# tinyha_power.net
KiCad netlist of a schematic drawn in EAGLE
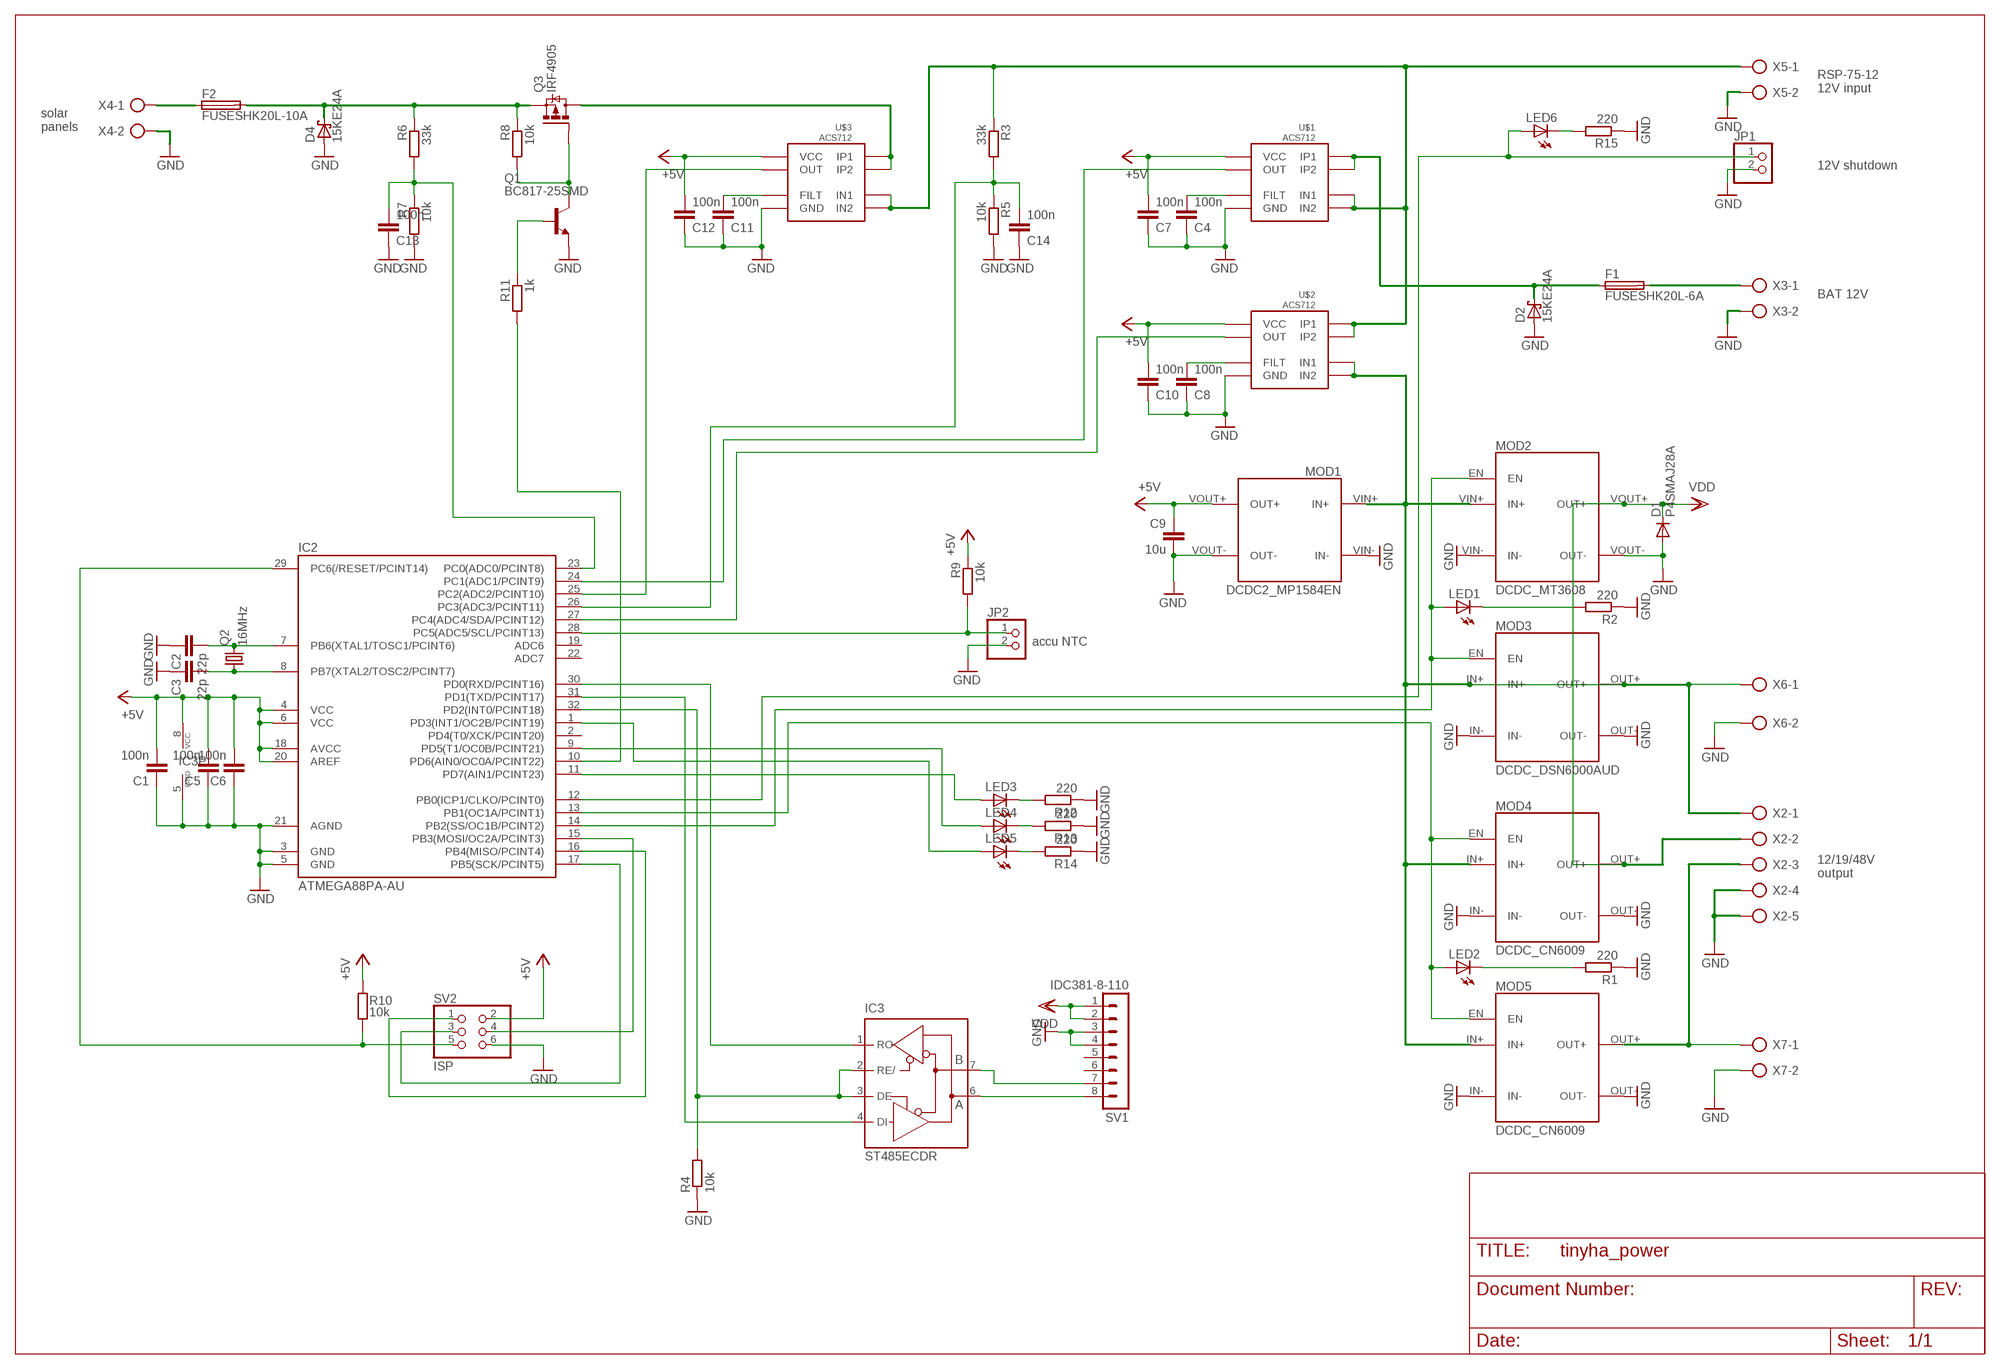
[diagram p0: schematic, sheet 1]

(export (version "E")
  (design (tool "Eeschema 10.0.6"))
  (components
    (comp (ref "C1")
      (value "100n")
      (footprint "eagle-import:C0805K")
      (libsource (lib "eagle-import") (part "C-EUC0805K"))
    )
    (comp (ref "C2")
      (value "22p")
      (footprint "eagle-import:C0805K")
      (libsource (lib "eagle-import") (part "C-EUC0805K"))
    )
    (comp (ref "C3")
      (value "22p")
      (footprint "eagle-import:C0805K")
      (libsource (lib "eagle-import") (part "C-EUC0805K"))
    )
    (comp (ref "C4")
      (value "100n")
      (footprint "eagle-import:C0805")
      (libsource (lib "eagle-import") (part "C-EUC0805"))
    )
    (comp (ref "C5")
      (value "100n")
      (footprint "eagle-import:C0805K")
      (libsource (lib "eagle-import") (part "C-EUC0805K"))
    )
    (comp (ref "C6")
      (value "100n")
      (footprint "eagle-import:C0805K")
      (libsource (lib "eagle-import") (part "C-EUC0805K"))
    )
    (comp (ref "C7")
      (value "100n")
      (footprint "eagle-import:C0805")
      (libsource (lib "eagle-import") (part "C-EUC0805"))
    )
    (comp (ref "C8")
      (value "100n")
      (footprint "eagle-import:C0805")
      (libsource (lib "eagle-import") (part "C-EUC0805"))
    )
    (comp (ref "C9")
      (value "10u")
      (footprint "eagle-import:C0805K")
      (libsource (lib "eagle-import") (part "C-EUC0805K"))
    )
    (comp (ref "C10")
      (value "100n")
      (footprint "eagle-import:C0805")
      (libsource (lib "eagle-import") (part "C-EUC0805"))
    )
    (comp (ref "C11")
      (value "100n")
      (footprint "eagle-import:C0805")
      (libsource (lib "eagle-import") (part "C-EUC0805"))
    )
    (comp (ref "C12")
      (value "100n")
      (footprint "eagle-import:C0805")
      (libsource (lib "eagle-import") (part "C-EUC0805"))
    )
    (comp (ref "C13")
      (value "100n")
      (footprint "eagle-import:C0805")
      (libsource (lib "eagle-import") (part "C-EUC0805"))
    )
    (comp (ref "C14")
      (value "100n")
      (footprint "eagle-import:C0805")
      (libsource (lib "eagle-import") (part "C-EUC0805"))
    )
    (comp (ref "D1")
      (value "P4SMAJ28A")
      (footprint "eagle-import:DO214AC")
      (libsource (lib "eagle-import") (part "DIODE-DO214AC"))
    )
    (comp (ref "D2")
      (value "15KE24A")
      (footprint "eagle-import:CB429-17")
      (libsource (lib "eagle-import") (part "15KEXX"))
    )
    (comp (ref "D4")
      (value "15KE24A")
      (footprint "eagle-import:CB429-17")
      (libsource (lib "eagle-import") (part "15KEXX"))
    )
    (comp (ref "F1")
      (value "FUSESHK20L-6A")
      (footprint "eagle-import:SHK20L")
      (libsource (lib "eagle-import") (part "FUSESHK20L"))
    )
    (comp (ref "F2")
      (value "FUSESHK20L-10A")
      (footprint "eagle-import:SHK20L")
      (libsource (lib "eagle-import") (part "FUSESHK20L"))
    )
    (comp (ref "IC2")
      (value "ATMEGA88PA-AU")
      (footprint "eagle-import:TQFP32-08")
      (libsource (lib "eagle-import") (part "ATMEGA48/88/168-AU"))
    )
    (comp (ref "IC3")
      (value "ST485ECDR")
      (footprint "eagle-import:SO08")
      (fields (field (name "MF") "MAXIM") (field (name "MPN") "MAX481CSA"))
      (libsource (lib "eagle-import") (part "MAX481CSA"))
    )
    (comp (ref "JP1")
      (value "PINHD-1X2")
      (footprint "eagle-import:1X02")
      (libsource (lib "eagle-import") (part "PINHD-1X2"))
    )
    (comp (ref "JP2")
      (value "PINHD-1X2")
      (footprint "eagle-import:1X02")
      (libsource (lib "eagle-import") (part "PINHD-1X2"))
    )
    (comp (ref "LED1")
      (value "LED3MM")
      (footprint "eagle-import:LED3MM")
      (libsource (lib "eagle-import") (part "LED3MM"))
    )
    (comp (ref "LED2")
      (value "LED3MM")
      (footprint "eagle-import:LED3MM")
      (libsource (lib "eagle-import") (part "LED3MM"))
    )
    (comp (ref "LED3")
      (value "LED3MM")
      (footprint "eagle-import:LED3MM")
      (libsource (lib "eagle-import") (part "LED3MM"))
    )
    (comp (ref "LED4")
      (value "LED3MM")
      (footprint "eagle-import:LED3MM")
      (libsource (lib "eagle-import") (part "LED3MM"))
    )
    (comp (ref "LED5")
      (value "LED3MM")
      (footprint "eagle-import:LED3MM")
      (libsource (lib "eagle-import") (part "LED3MM"))
    )
    (comp (ref "LED6")
      (value "LED3MM")
      (footprint "eagle-import:LED3MM")
      (libsource (lib "eagle-import") (part "LED3MM"))
    )
    (comp (ref "MOD1")
      (value "DCDC2_MP1584EN")
      (footprint "eagle-import:DCDC_MP1584EN")
      (libsource (lib "eagle-import") (part "DCDC2_MP1584EN"))
    )
    (comp (ref "MOD2")
      (value "DCDC_MT3608")
      (footprint "eagle-import:DCDC_MT3608")
      (libsource (lib "eagle-import") (part "DCDC_MT3608"))
    )
    (comp (ref "MOD3")
      (value "DCDC_DSN6000AUD")
      (footprint "eagle-import:DCDC_DSN6000AUD")
      (libsource (lib "eagle-import") (part "DCDC_DSN6000AUD"))
    )
    (comp (ref "MOD4")
      (value "DCDC_CN6009")
      (footprint "eagle-import:DCDC_CN6009")
      (libsource (lib "eagle-import") (part "DCDC_CN6009"))
    )
    (comp (ref "MOD5")
      (value "DCDC_CN6009")
      (footprint "eagle-import:DCDC_CN6009")
      (libsource (lib "eagle-import") (part "DCDC_CN6009"))
    )
    (comp (ref "Q1")
      (value "BC817-25SMD")
      (footprint "eagle-import:SOT23-BEC")
      (libsource (lib "eagle-import") (part "BC817SMD-25"))
    )
    (comp (ref "Q2")
      (value "16MHz")
      (footprint "eagle-import:HC49_S")
      (libsource (lib "eagle-import") (part "CRYSTALHC49S"))
    )
    (comp (ref "Q3")
      (value "IRF4905")
      (footprint "eagle-import:TO220BH")
      (libsource (lib "eagle-import") (part "IRF4905"))
    )
    (comp (ref "R1")
      (value "220")
      (footprint "eagle-import:R0805")
      (libsource (lib "eagle-import") (part "R-EU_R0805"))
    )
    (comp (ref "R2")
      (value "220")
      (footprint "eagle-import:R0805")
      (libsource (lib "eagle-import") (part "R-EU_R0805"))
    )
    (comp (ref "R3")
      (value "33k")
      (footprint "eagle-import:R0805")
      (libsource (lib "eagle-import") (part "R-EU_R0805"))
    )
    (comp (ref "R4")
      (value "10k")
      (footprint "eagle-import:R0805")
      (libsource (lib "eagle-import") (part "R-EU_R0805"))
    )
    (comp (ref "R5")
      (value "10k")
      (footprint "eagle-import:R0805")
      (libsource (lib "eagle-import") (part "R-EU_R0805"))
    )
    (comp (ref "R6")
      (value "33k")
      (footprint "eagle-import:R0805")
      (libsource (lib "eagle-import") (part "R-EU_R0805"))
    )
    (comp (ref "R7")
      (value "10k")
      (footprint "eagle-import:R0805")
      (libsource (lib "eagle-import") (part "R-EU_R0805"))
    )
    (comp (ref "R8")
      (value "10k")
      (footprint "eagle-import:R0805")
      (libsource (lib "eagle-import") (part "R-EU_R0805"))
    )
    (comp (ref "R9")
      (value "10k")
      (footprint "eagle-import:R0805")
      (libsource (lib "eagle-import") (part "R-EU_R0805"))
    )
    (comp (ref "R10")
      (value "10k")
      (footprint "eagle-import:R0805")
      (libsource (lib "eagle-import") (part "R-EU_R0805"))
    )
    (comp (ref "R11")
      (value "1k")
      (footprint "eagle-import:R0805")
      (libsource (lib "eagle-import") (part "R-EU_R0805"))
    )
    (comp (ref "R12")
      (value "220")
      (footprint "eagle-import:R0805")
      (libsource (lib "eagle-import") (part "R-EU_R0805"))
    )
    (comp (ref "R13")
      (value "220")
      (footprint "eagle-import:R0805")
      (libsource (lib "eagle-import") (part "R-EU_R0805"))
    )
    (comp (ref "R14")
      (value "220")
      (footprint "eagle-import:R0805")
      (libsource (lib "eagle-import") (part "R-EU_R0805"))
    )
    (comp (ref "R15")
      (value "220")
      (footprint "eagle-import:R0805")
      (libsource (lib "eagle-import") (part "R-EU_R0805"))
    )
    (comp (ref "SV1")
      (value "IDC381-8-110")
      (footprint "eagle-import:IDC381-8")
      (libsource (lib "eagle-import") (part "MA08-1-IDC"))
    )
    (comp (ref "SV2")
      (value "ISP")
      (footprint "eagle-import:2X03_H")
      (libsource (lib "eagle-import") (part "PINHD-2X3/H"))
    )
    (comp (ref "U$1")
      (value "ACS712")
      (footprint "eagle-import:SO8")
      (libsource (lib "eagle-import") (part "ACS712"))
    )
    (comp (ref "U$2")
      (value "ACS712")
      (footprint "eagle-import:SO8")
      (libsource (lib "eagle-import") (part "ACS712"))
    )
    (comp (ref "U$3")
      (value "ACS712")
      (footprint "eagle-import:SO8")
      (libsource (lib "eagle-import") (part "ACS712"))
    )
    (comp (ref "X2")
      (value "AK500/5")
      (footprint "eagle-import:AK500_5")
      (libsource (lib "eagle-import") (part "AK500/5"))
    )
    (comp (ref "X3")
      (value "AK500/2")
      (footprint "eagle-import:AK500_2")
      (libsource (lib "eagle-import") (part "AK500/2"))
    )
    (comp (ref "X4")
      (value "AK500/2")
      (footprint "eagle-import:AK500_2")
      (libsource (lib "eagle-import") (part "AK500/2"))
    )
    (comp (ref "X5")
      (value "AK500/2")
      (footprint "eagle-import:AK500_2")
      (libsource (lib "eagle-import") (part "AK500/2"))
    )
    (comp (ref "X6")
      (value "AK500/2")
      (footprint "eagle-import:AK500_2")
      (libsource (lib "eagle-import") (part "AK500/2"))
    )
    (comp (ref "X7")
      (value "AK500/2")
      (footprint "eagle-import:AK500_2")
      (libsource (lib "eagle-import") (part "AK500/2"))
    )
  )
  (nets
    (net (code "1") (name "+5V") (class "Default")
      (node (ref "C1") (pin "2") (pinfunction "2_2") (pintype "passive"))
      (node (ref "C10") (pin "2") (pinfunction "2_2") (pintype "passive"))
      (node (ref "C12") (pin "2") (pinfunction "2_2") (pintype "passive"))
      (node (ref "C5") (pin "2") (pinfunction "2_2") (pintype "passive"))
      (node (ref "C6") (pin "2") (pinfunction "2_2") (pintype "passive"))
      (node (ref "C7") (pin "2") (pinfunction "2_2") (pintype "passive"))
      (node (ref "C9") (pin "1") (pinfunction "1_1") (pintype "passive"))
      (node (ref "IC2") (pin "18") (pinfunction "AVCC_18") (pintype "passive"))
      (node (ref "IC2") (pin "20") (pinfunction "AREF_20") (pintype "passive"))
      (node (ref "IC2") (pin "4") (pinfunction "VCC_4") (pintype "power_in"))
      (node (ref "IC2") (pin "6") (pinfunction "VCC_6") (pintype "power_in"))
      (node (ref "IC3") (pin "8") (pinfunction "VCC_8") (pintype "power_in"))
      (node (ref "MOD1") (pin "VOUT+") (pinfunction "OUT+_VOUT+") (pintype "passive"))
      (node (ref "R10") (pin "1") (pinfunction "1_1") (pintype "passive"))
      (node (ref "R9") (pin "1") (pinfunction "1_1") (pintype "passive"))
      (node (ref "SV2") (pin "2") (pinfunction "2_2") (pintype "passive"))
      (node (ref "U$1") (pin "8") (pinfunction "VCC_8") (pintype "bidirectional"))
      (node (ref "U$2") (pin "8") (pinfunction "VCC_8") (pintype "bidirectional"))
      (node (ref "U$3") (pin "8") (pinfunction "VCC_8") (pintype "bidirectional"))
    )
    (net (code "2") (name "GND") (class "Default")
      (node (ref "C1") (pin "1") (pinfunction "1_1") (pintype "passive"))
      (node (ref "C10") (pin "1") (pinfunction "1_1") (pintype "passive"))
      (node (ref "C11") (pin "1") (pinfunction "1_1") (pintype "passive"))
      (node (ref "C12") (pin "1") (pinfunction "1_1") (pintype "passive"))
      (node (ref "C13") (pin "1") (pinfunction "1_1") (pintype "passive"))
      (node (ref "C14") (pin "1") (pinfunction "1_1") (pintype "passive"))
      (node (ref "C2") (pin "1") (pinfunction "1_1") (pintype "passive"))
      (node (ref "C3") (pin "1") (pinfunction "1_1") (pintype "passive"))
      (node (ref "C4") (pin "1") (pinfunction "1_1") (pintype "passive"))
      (node (ref "C5") (pin "1") (pinfunction "1_1") (pintype "passive"))
      (node (ref "C6") (pin "1") (pinfunction "1_1") (pintype "passive"))
      (node (ref "C7") (pin "1") (pinfunction "1_1") (pintype "passive"))
      (node (ref "C8") (pin "1") (pinfunction "1_1") (pintype "passive"))
      (node (ref "C9") (pin "2") (pinfunction "2_2") (pintype "passive"))
      (node (ref "D1") (pin "A") (pinfunction "A_A") (pintype "passive"))
      (node (ref "D2") (pin "A") (pinfunction "A_A") (pintype "passive"))
      (node (ref "D4") (pin "A") (pinfunction "A_A") (pintype "passive"))
      (node (ref "IC2") (pin "21") (pinfunction "AGND_21") (pintype "power_in"))
      (node (ref "IC2") (pin "3") (pinfunction "GND_3") (pintype "power_in"))
      (node (ref "IC2") (pin "5") (pinfunction "GND_5") (pintype "power_in"))
      (node (ref "IC3") (pin "5") (pinfunction "GND_5") (pintype "power_in"))
      (node (ref "JP1") (pin "2") (pinfunction "2_2") (pintype "passive"))
      (node (ref "JP2") (pin "2") (pinfunction "2_2") (pintype "passive"))
      (node (ref "MOD1") (pin "VIN-") (pinfunction "IN-_VIN-") (pintype "passive"))
      (node (ref "MOD1") (pin "VOUT-") (pinfunction "OUT-_VOUT-") (pintype "passive"))
      (node (ref "MOD2") (pin "VIN-") (pinfunction "IN-_VIN-") (pintype "passive"))
      (node (ref "MOD2") (pin "VOUT-") (pinfunction "OUT-_VOUT-") (pintype "passive"))
      (node (ref "MOD3") (pin "IN-") (pinfunction "IN-_IN-") (pintype "passive"))
      (node (ref "MOD3") (pin "OUT-") (pinfunction "OUT-_OUT-") (pintype "passive"))
      (node (ref "MOD4") (pin "IN-") (pinfunction "IN-_IN-") (pintype "passive"))
      (node (ref "MOD4") (pin "OUT-") (pinfunction "OUT-_OUT-") (pintype "passive"))
      (node (ref "MOD5") (pin "IN-") (pinfunction "IN-_IN-") (pintype "passive"))
      (node (ref "MOD5") (pin "OUT-") (pinfunction "OUT-_OUT-") (pintype "passive"))
      (node (ref "Q1") (pin "E") (pinfunction "E_E") (pintype "passive"))
      (node (ref "R1") (pin "1") (pinfunction "1_1") (pintype "passive"))
      (node (ref "R12") (pin "1") (pinfunction "1_1") (pintype "passive"))
      (node (ref "R13") (pin "1") (pinfunction "1_1") (pintype "passive"))
      (node (ref "R14") (pin "1") (pinfunction "1_1") (pintype "passive"))
      (node (ref "R15") (pin "1") (pinfunction "1_1") (pintype "passive"))
      (node (ref "R2") (pin "1") (pinfunction "1_1") (pintype "passive"))
      (node (ref "R4") (pin "1") (pinfunction "1_1") (pintype "passive"))
      (node (ref "R5") (pin "2") (pinfunction "2_2") (pintype "passive"))
      (node (ref "R7") (pin "2") (pinfunction "2_2") (pintype "passive"))
      (node (ref "SV1") (pin "3") (pinfunction "3_3") (pintype "passive"))
      (node (ref "SV1") (pin "4") (pinfunction "4_4") (pintype "passive"))
      (node (ref "SV2") (pin "6") (pinfunction "6_6") (pintype "passive"))
      (node (ref "U$1") (pin "5") (pinfunction "GND_5") (pintype "bidirectional"))
      (node (ref "U$2") (pin "5") (pinfunction "GND_5") (pintype "bidirectional"))
      (node (ref "U$3") (pin "5") (pinfunction "GND_5") (pintype "bidirectional"))
      (node (ref "X2") (pin "4") (pinfunction "KL_4") (pintype "passive"))
      (node (ref "X2") (pin "5") (pinfunction "KL_5") (pintype "passive"))
      (node (ref "X3") (pin "2") (pinfunction "KL_2") (pintype "passive"))
      (node (ref "X4") (pin "2") (pinfunction "KL_2") (pintype "passive"))
      (node (ref "X5") (pin "2") (pinfunction "KL_2") (pintype "passive"))
      (node (ref "X6") (pin "2") (pinfunction "KL_2") (pintype "passive"))
      (node (ref "X7") (pin "2") (pinfunction "KL_2") (pintype "passive"))
    )
    (net (code "3") (name "Net-(F1-1)") (class "Default")
      (node (ref "D2") (pin "C") (pinfunction "C_C") (pintype "passive"))
      (node (ref "F1") (pin "1A") (pinfunction "1_1A") (pintype "passive"))
      (node (ref "U$1") (pin "1") (pinfunction "IP1_1") (pintype "bidirectional"))
      (node (ref "U$1") (pin "2") (pinfunction "IP2_2") (pintype "bidirectional"))
    )
    (net (code "4") (name "Net-(F1-2)") (class "Default")
      (node (ref "F1") (pin "2A") (pinfunction "2_2A") (pintype "passive"))
      (node (ref "X3") (pin "1") (pinfunction "KL_1") (pintype "passive"))
    )
    (net (code "5") (name "Net-(F2-1)") (class "Default")
      (node (ref "F2") (pin "1A") (pinfunction "1_1A") (pintype "passive"))
      (node (ref "X4") (pin "1") (pinfunction "KL_1") (pintype "passive"))
    )
    (net (code "6") (name "Net-(F2-2)") (class "Default")
      (node (ref "D4") (pin "C") (pinfunction "C_C") (pintype "passive"))
      (node (ref "F2") (pin "2A") (pinfunction "2_2A") (pintype "passive"))
      (node (ref "Q3") (pin "S") (pinfunction "S_S") (pintype "passive"))
      (node (ref "R6") (pin "1") (pinfunction "1_1") (pintype "passive"))
      (node (ref "R8") (pin "1") (pinfunction "1_1") (pintype "passive"))
    )
    (net (code "7") (name "Net-(IC2-PB0(ICP1{slash}CLKO{slash}PCINT0))") (class "Default")
      (node (ref "IC2") (pin "12") (pinfunction "PB0(ICP1/CLKO/PCINT0)_12") (pintype "bidirectional"))
      (node (ref "JP1") (pin "1") (pinfunction "1_1") (pintype "passive"))
      (node (ref "LED6") (pin "A") (pinfunction "A_A") (pintype "passive"))
    )
    (net (code "8") (name "Net-(IC2-PB1(OC1A{slash}PCINT1))") (class "Default")
      (node (ref "IC2") (pin "13") (pinfunction "PB1(OC1A/PCINT1)_13") (pintype "bidirectional"))
      (node (ref "LED2") (pin "A") (pinfunction "A_A") (pintype "passive"))
      (node (ref "MOD4") (pin "EN") (pinfunction "EN_EN") (pintype "input"))
      (node (ref "MOD5") (pin "EN") (pinfunction "EN_EN") (pintype "input"))
    )
    (net (code "9") (name "Net-(IC2-PB2(SS{slash}OC1B{slash}PCINT2))") (class "Default")
      (node (ref "IC2") (pin "14") (pinfunction "PB2(SS/OC1B/PCINT2)_14") (pintype "bidirectional"))
      (node (ref "LED1") (pin "A") (pinfunction "A_A") (pintype "passive"))
      (node (ref "MOD2") (pin "EN") (pinfunction "EN_EN") (pintype "input"))
      (node (ref "MOD3") (pin "EN") (pinfunction "EN_EN") (pintype "input"))
    )
    (net (code "10") (name "Net-(IC2-PB3(MOSI{slash}OC2A{slash}PCINT3))") (class "Default")
      (node (ref "IC2") (pin "15") (pinfunction "PB3(MOSI/OC2A/PCINT3)_15") (pintype "bidirectional"))
      (node (ref "SV2") (pin "4") (pinfunction "4_4") (pintype "passive"))
    )
    (net (code "11") (name "Net-(IC2-PB4(MISO{slash}PCINT4))") (class "Default")
      (node (ref "IC2") (pin "16") (pinfunction "PB4(MISO/PCINT4)_16") (pintype "bidirectional"))
      (node (ref "SV2") (pin "1") (pinfunction "1_1") (pintype "passive"))
    )
    (net (code "12") (name "Net-(IC2-PB5(SCK{slash}PCINT5))") (class "Default")
      (node (ref "IC2") (pin "17") (pinfunction "PB5(SCK/PCINT5)_17") (pintype "bidirectional"))
      (node (ref "SV2") (pin "3") (pinfunction "3_3") (pintype "passive"))
    )
    (net (code "13") (name "Net-(IC2-PB6(XTAL1{slash}TOSC1{slash}PCINT6))") (class "Default")
      (node (ref "C2") (pin "2") (pinfunction "2_2") (pintype "passive"))
      (node (ref "IC2") (pin "7") (pinfunction "PB6(XTAL1/TOSC1/PCINT6)_7") (pintype "bidirectional"))
      (node (ref "Q2") (pin "2") (pinfunction "2_2") (pintype "passive"))
    )
    (net (code "14") (name "Net-(IC2-PB7(XTAL2{slash}TOSC2{slash}PCINT7))") (class "Default")
      (node (ref "C3") (pin "2") (pinfunction "2_2") (pintype "passive"))
      (node (ref "IC2") (pin "8") (pinfunction "PB7(XTAL2/TOSC2/PCINT7)_8") (pintype "bidirectional"))
      (node (ref "Q2") (pin "1") (pinfunction "1_1") (pintype "passive"))
    )
    (net (code "15") (name "Net-(IC2-PC0(ADC0{slash}PCINT8))") (class "Default")
      (node (ref "C13") (pin "2") (pinfunction "2_2") (pintype "passive"))
      (node (ref "IC2") (pin "23") (pinfunction "PC0(ADC0/PCINT8)_23") (pintype "bidirectional"))
      (node (ref "R6") (pin "2") (pinfunction "2_2") (pintype "passive"))
      (node (ref "R7") (pin "1") (pinfunction "1_1") (pintype "passive"))
    )
    (net (code "16") (name "Net-(IC2-PC1(ADC1{slash}PCINT9))") (class "Default")
      (node (ref "IC2") (pin "24") (pinfunction "PC1(ADC1/PCINT9)_24") (pintype "bidirectional"))
      (node (ref "U$1") (pin "7") (pinfunction "OUT_7") (pintype "bidirectional"))
    )
    (net (code "17") (name "Net-(IC2-PC2(ADC2{slash}PCINT10))") (class "Default")
      (node (ref "IC2") (pin "25") (pinfunction "PC2(ADC2/PCINT10)_25") (pintype "bidirectional"))
      (node (ref "U$3") (pin "7") (pinfunction "OUT_7") (pintype "bidirectional"))
    )
    (net (code "18") (name "Net-(IC2-PC3(ADC3{slash}PCINT11))") (class "Default")
      (node (ref "C14") (pin "2") (pinfunction "2_2") (pintype "passive"))
      (node (ref "IC2") (pin "26") (pinfunction "PC3(ADC3/PCINT11)_26") (pintype "bidirectional"))
      (node (ref "R3") (pin "2") (pinfunction "2_2") (pintype "passive"))
      (node (ref "R5") (pin "1") (pinfunction "1_1") (pintype "passive"))
    )
    (net (code "19") (name "Net-(IC2-PC4(ADC4{slash}SDA{slash}PCINT12))") (class "Default")
      (node (ref "IC2") (pin "27") (pinfunction "PC4(ADC4/SDA/PCINT12)_27") (pintype "bidirectional"))
      (node (ref "U$2") (pin "7") (pinfunction "OUT_7") (pintype "bidirectional"))
    )
    (net (code "20") (name "Net-(IC2-PC5(ADC5{slash}SCL{slash}PCINT13))") (class "Default")
      (node (ref "IC2") (pin "28") (pinfunction "PC5(ADC5/SCL/PCINT13)_28") (pintype "bidirectional"))
      (node (ref "JP2") (pin "1") (pinfunction "1_1") (pintype "passive"))
      (node (ref "R9") (pin "2") (pinfunction "2_2") (pintype "passive"))
    )
    (net (code "21") (name "Net-(IC2-PC6({slash}RESET{slash}PCINT14))") (class "Default")
      (node (ref "IC2") (pin "29") (pinfunction "PC6(/RESET/PCINT14)_29") (pintype "bidirectional"))
      (node (ref "R10") (pin "2") (pinfunction "2_2") (pintype "passive"))
      (node (ref "SV2") (pin "5") (pinfunction "5_5") (pintype "passive"))
    )
    (net (code "22") (name "Net-(IC2-PD0(RXD{slash}PCINT16))") (class "Default")
      (node (ref "IC2") (pin "30") (pinfunction "PD0(RXD/PCINT16)_30") (pintype "bidirectional"))
      (node (ref "IC3") (pin "1") (pinfunction "RO_1") (pintype "output"))
    )
    (net (code "23") (name "Net-(IC2-PD1(TXD{slash}PCINT17))") (class "Default")
      (node (ref "IC2") (pin "31") (pinfunction "PD1(TXD/PCINT17)_31") (pintype "bidirectional"))
      (node (ref "IC3") (pin "4") (pinfunction "DI_4") (pintype "input"))
    )
    (net (code "24") (name "Net-(IC2-PD2(INT0{slash}PCINT18))") (class "Default")
      (node (ref "IC2") (pin "32") (pinfunction "PD2(INT0/PCINT18)_32") (pintype "bidirectional"))
      (node (ref "IC3") (pin "2") (pinfunction "RE/_2") (pintype "input"))
      (node (ref "IC3") (pin "3") (pinfunction "DE_3") (pintype "input"))
      (node (ref "R4") (pin "2") (pinfunction "2_2") (pintype "passive"))
    )
    (net (code "25") (name "Net-(IC2-PD3(INT1{slash}OC2B{slash}PCINT19))") (class "Default")
      (node (ref "IC2") (pin "1") (pinfunction "PD3(INT1/OC2B/PCINT19)_1") (pintype "bidirectional"))
      (node (ref "LED5") (pin "A") (pinfunction "A_A") (pintype "passive"))
    )
    (net (code "26") (name "Net-(IC2-PD5(T1{slash}OC0B{slash}PCINT21))") (class "Default")
      (node (ref "IC2") (pin "9") (pinfunction "PD5(T1/OC0B/PCINT21)_9") (pintype "bidirectional"))
      (node (ref "LED4") (pin "A") (pinfunction "A_A") (pintype "passive"))
    )
    (net (code "27") (name "Net-(IC2-PD6(AIN0{slash}OC0A{slash}PCINT22))") (class "Default")
      (node (ref "IC2") (pin "10") (pinfunction "PD6(AIN0/OC0A/PCINT22)_10") (pintype "bidirectional"))
      (node (ref "R11") (pin "2") (pinfunction "2_2") (pintype "passive"))
    )
    (net (code "28") (name "Net-(IC2-PD7(AIN1{slash}PCINT23))") (class "Default")
      (node (ref "IC2") (pin "11") (pinfunction "PD7(AIN1/PCINT23)_11") (pintype "bidirectional"))
      (node (ref "LED3") (pin "A") (pinfunction "A_A") (pintype "passive"))
    )
    (net (code "29") (name "Net-(IC3A-A)") (class "Default")
      (node (ref "IC3") (pin "6") (pinfunction "A_6") (pintype "passive"))
      (node (ref "SV1") (pin "8") (pinfunction "8_8") (pintype "passive"))
    )
    (net (code "30") (name "Net-(IC3A-B)") (class "Default")
      (node (ref "IC3") (pin "7") (pinfunction "B_7") (pintype "passive"))
      (node (ref "SV1") (pin "7") (pinfunction "7_7") (pintype "passive"))
    )
    (net (code "31") (name "Net-(LED1-C)") (class "Default")
      (node (ref "LED1") (pin "K") (pinfunction "C_K") (pintype "passive"))
      (node (ref "R2") (pin "2") (pinfunction "2_2") (pintype "passive"))
    )
    (net (code "32") (name "Net-(LED2-C)") (class "Default")
      (node (ref "LED2") (pin "K") (pinfunction "C_K") (pintype "passive"))
      (node (ref "R1") (pin "2") (pinfunction "2_2") (pintype "passive"))
    )
    (net (code "33") (name "Net-(LED3-C)") (class "Default")
      (node (ref "LED3") (pin "K") (pinfunction "C_K") (pintype "passive"))
      (node (ref "R12") (pin "2") (pinfunction "2_2") (pintype "passive"))
    )
    (net (code "34") (name "Net-(LED4-C)") (class "Default")
      (node (ref "LED4") (pin "K") (pinfunction "C_K") (pintype "passive"))
      (node (ref "R13") (pin "2") (pinfunction "2_2") (pintype "passive"))
    )
    (net (code "35") (name "Net-(LED5-C)") (class "Default")
      (node (ref "LED5") (pin "K") (pinfunction "C_K") (pintype "passive"))
      (node (ref "R14") (pin "2") (pinfunction "2_2") (pintype "passive"))
    )
    (net (code "36") (name "Net-(LED6-C)") (class "Default")
      (node (ref "LED6") (pin "K") (pinfunction "C_K") (pintype "passive"))
      (node (ref "R15") (pin "2") (pinfunction "2_2") (pintype "passive"))
    )
    (net (code "37") (name "Net-(MOD1-IN+)") (class "Default")
      (node (ref "MOD1") (pin "VIN+") (pinfunction "IN+_VIN+") (pintype "passive"))
      (node (ref "MOD2") (pin "VIN+") (pinfunction "IN+_VIN+") (pintype "passive"))
      (node (ref "MOD3") (pin "IN+") (pinfunction "IN+_IN+") (pintype "passive"))
      (node (ref "MOD3") (pin "OUT+") (pinfunction "OUT+_OUT+") (pintype "passive"))
      (node (ref "MOD4") (pin "IN+") (pinfunction "IN+_IN+") (pintype "passive"))
      (node (ref "MOD5") (pin "IN+") (pinfunction "IN+_IN+") (pintype "passive"))
      (node (ref "U$2") (pin "3") (pinfunction "IN1_3") (pintype "bidirectional"))
      (node (ref "U$2") (pin "4") (pinfunction "IN2_4") (pintype "bidirectional"))
      (node (ref "X2") (pin "1") (pinfunction "KL_1") (pintype "passive"))
      (node (ref "X6") (pin "1") (pinfunction "KL_1") (pintype "passive"))
    )
    (net (code "38") (name "Net-(Q1-PadB)") (class "Default")
      (node (ref "Q1") (pin "B") (pinfunction "B_B") (pintype "passive"))
      (node (ref "R11") (pin "1") (pinfunction "1_1") (pintype "passive"))
    )
    (net (code "39") (name "Net-(Q1-PadC)") (class "Default")
      (node (ref "Q1") (pin "C") (pinfunction "C_C") (pintype "passive"))
      (node (ref "Q3") (pin "G") (pinfunction "G_G") (pintype "passive"))
      (node (ref "R8") (pin "2") (pinfunction "2_2") (pintype "passive"))
    )
    (net (code "40") (name "Net-(U$1-FILT)") (class "Default")
      (node (ref "C4") (pin "2") (pinfunction "2_2") (pintype "passive"))
      (node (ref "U$1") (pin "6") (pinfunction "FILT_6") (pintype "bidirectional"))
    )
    (net (code "41") (name "Net-(U$1-IN1)") (class "Default")
      (node (ref "R3") (pin "1") (pinfunction "1_1") (pintype "passive"))
      (node (ref "U$1") (pin "3") (pinfunction "IN1_3") (pintype "bidirectional"))
      (node (ref "U$1") (pin "4") (pinfunction "IN2_4") (pintype "bidirectional"))
      (node (ref "U$2") (pin "1") (pinfunction "IP1_1") (pintype "bidirectional"))
      (node (ref "U$2") (pin "2") (pinfunction "IP2_2") (pintype "bidirectional"))
      (node (ref "U$3") (pin "3") (pinfunction "IN1_3") (pintype "bidirectional"))
      (node (ref "U$3") (pin "4") (pinfunction "IN2_4") (pintype "bidirectional"))
      (node (ref "X5") (pin "1") (pinfunction "KL_1") (pintype "passive"))
    )
    (net (code "42") (name "Net-(U$2-FILT)") (class "Default")
      (node (ref "C8") (pin "2") (pinfunction "2_2") (pintype "passive"))
      (node (ref "U$2") (pin "6") (pinfunction "FILT_6") (pintype "bidirectional"))
    )
    (net (code "43") (name "Net-(U$3-FILT)") (class "Default")
      (node (ref "C11") (pin "2") (pinfunction "2_2") (pintype "passive"))
      (node (ref "U$3") (pin "6") (pinfunction "FILT_6") (pintype "bidirectional"))
    )
    (net (code "44") (name "Net-(U$3-IP1)") (class "Default")
      (node (ref "Q3") (pin "D") (pinfunction "D_D") (pintype "passive"))
      (node (ref "U$3") (pin "1") (pinfunction "IP1_1") (pintype "bidirectional"))
      (node (ref "U$3") (pin "2") (pinfunction "IP2_2") (pintype "bidirectional"))
    )
    (net (code "45") (name "Net-(X2C-KL)") (class "Default")
      (node (ref "MOD5") (pin "OUT+") (pinfunction "OUT+_OUT+") (pintype "passive"))
      (node (ref "X2") (pin "3") (pinfunction "KL_3") (pintype "passive"))
      (node (ref "X7") (pin "1") (pinfunction "KL_1") (pintype "passive"))
    )
    (net (code "46") (name "VDD") (class "Default")
      (node (ref "D1") (pin "C") (pinfunction "C_C") (pintype "passive"))
      (node (ref "MOD2") (pin "VOUT+") (pinfunction "OUT+_VOUT+") (pintype "passive"))
      (node (ref "MOD4") (pin "OUT+") (pinfunction "OUT+_OUT+") (pintype "passive"))
      (node (ref "SV1") (pin "1") (pinfunction "1_1") (pintype "passive"))
      (node (ref "SV1") (pin "2") (pinfunction "2_2") (pintype "passive"))
      (node (ref "X2") (pin "2") (pinfunction "KL_2") (pintype "passive"))
    )
    (net (code "47") (name "unconnected-(IC2-ADC6-Pad19)") (class "Default")
      (node (ref "IC2") (pin "19") (pinfunction "ADC6_19") (pintype "passive"))
    )
    (net (code "48") (name "unconnected-(IC2-ADC7-Pad22)") (class "Default")
      (node (ref "IC2") (pin "22") (pinfunction "ADC7_22") (pintype "passive"))
    )
    (net (code "49") (name "unconnected-(IC2-PD4(T0{slash}XCK{slash}PCINT20)-Pad2)") (class "Default")
      (node (ref "IC2") (pin "2") (pinfunction "PD4(T0/XCK/PCINT20)_2") (pintype "bidirectional"))
    )
    (net (code "50") (name "unconnected-(SV1-Pad5)") (class "Default")
      (node (ref "SV1") (pin "5") (pinfunction "5_5") (pintype "passive"))
    )
    (net (code "51") (name "unconnected-(SV1-Pad6)") (class "Default")
      (node (ref "SV1") (pin "6") (pinfunction "6_6") (pintype "passive"))
    )
  )
)
